# sensor_eeprom_v3_0.net
KiCad netlist of a schematic drawn in EAGLE
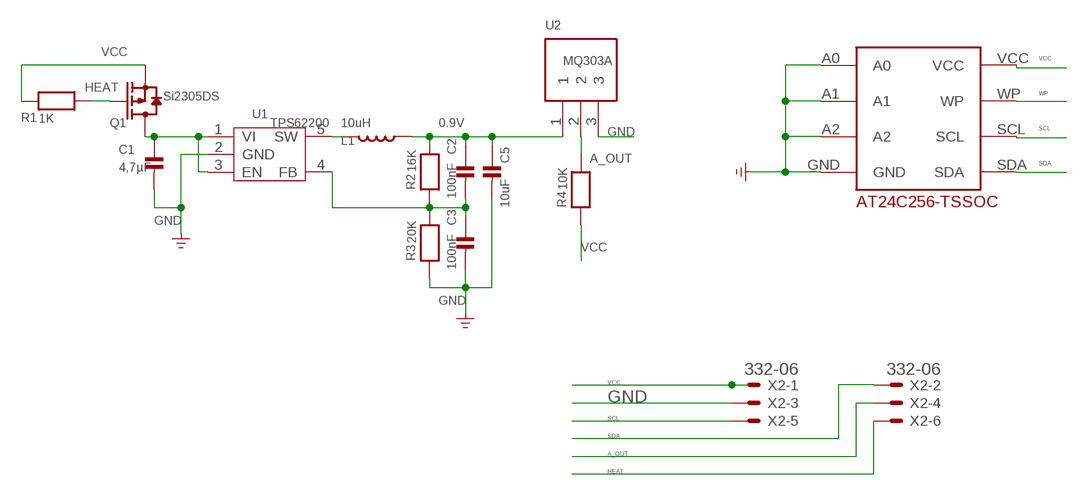
[diagram p0: schematic, sheet 1]

(export (version "E")
  (design (tool "Eeschema 10.0.6"))
  (components
    (comp (ref "C1")
      (value "4,7µF")
      (footprint "eagle-import:0805")
      (libsource (lib "eagle-import") (part "CAP_CERAMIC0805"))
    )
    (comp (ref "C2")
      (value "100nF")
      (footprint "eagle-import:0805")
      (libsource (lib "eagle-import") (part "CAP_CERAMIC0805"))
    )
    (comp (ref "C3")
      (value "100nF")
      (footprint "eagle-import:0805")
      (libsource (lib "eagle-import") (part "CAP_CERAMIC0805"))
    )
    (comp (ref "C5")
      (value "10uF")
      (footprint "eagle-import:0805")
      (libsource (lib "eagle-import") (part "CAP_CERAMIC0805"))
    )
    (comp (ref "L1")
      (value "10uH")
      (footprint "eagle-import:PIO73")
      (libsource (lib "eagle-import") (part "L'PIO73'"))
    )
    (comp (ref "Q1")
      (value "Si2305DS")
      (footprint "eagle-import:SOT23")
      (libsource (lib "eagle-import") (part "MOSFET-P'SI2323CDS/SI2305DS{lt}BR{gt}'"))
    )
    (comp (ref "R1")
      (value "1K")
      (footprint "eagle-import:0805")
      (libsource (lib "eagle-import") (part "RESISTOR0805"))
    )
    (comp (ref "R2")
      (value "16K")
      (footprint "eagle-import:0805")
      (libsource (lib "eagle-import") (part "RESISTOR0805"))
    )
    (comp (ref "R3")
      (value "20K")
      (footprint "eagle-import:0805")
      (libsource (lib "eagle-import") (part "RESISTOR0805"))
    )
    (comp (ref "R4")
      (value "10K")
      (footprint "eagle-import:0805")
      (libsource (lib "eagle-import") (part "RESISTOR0805"))
    )
    (comp (ref "U$1")
      (value "DECADE-AT24C256-10TI-2.7")
      (footprint "eagle-import:DECADE-AT24CXX")
      (libsource (lib "eagle-import") (part "DECADE-AT24C256-10TI-2.7"))
    )
    (comp (ref "U1")
      (value "TPS62200")
      (footprint "eagle-import:SOT23-5")
      (libsource (lib "eagle-import") (part "TPS62200DBV"))
    )
    (comp (ref "U2")
      (value "MQ303A")
      (footprint "eagle-import:MQ303A")
      (libsource (lib "eagle-import") (part "MQ303A"))
    )
    (comp (ref "X2")
      (value "332-06")
      (footprint "eagle-import:332-06")
      (libsource (lib "eagle-import") (part "332-06"))
    )
  )
  (nets
    (net (code "1") (name "/0.9V") (class "Default")
      (node (ref "C2") (pin "1") (pinfunction "P$1_1") (pintype "passive"))
      (node (ref "C5") (pin "1") (pinfunction "P$1_1") (pintype "passive"))
      (node (ref "L1") (pin "2") (pinfunction "2_2") (pintype "passive"))
      (node (ref "R2") (pin "2") (pinfunction "2_2") (pintype "passive"))
      (node (ref "U2") (pin "1") (pinfunction "1_1") (pintype "bidirectional"))
    )
    (net (code "2") (name "/A_OUT") (class "Default")
      (node (ref "R4") (pin "2") (pinfunction "2_2") (pintype "passive"))
      (node (ref "U2") (pin "2") (pinfunction "2_2") (pintype "bidirectional"))
      (node (ref "X2") (pin "4") (pinfunction "S_4") (pintype "passive"))
    )
    (net (code "3") (name "/HEAT") (class "Default")
      (node (ref "Q1") (pin "1") (pinfunction "G_1") (pintype "passive"))
      (node (ref "R1") (pin "2") (pinfunction "2_2") (pintype "passive"))
      (node (ref "X2") (pin "6") (pinfunction "S_6") (pintype "passive"))
    )
    (net (code "4") (name "/SCL") (class "Default")
      (node (ref "U$1") (pin "SCL") (pinfunction "SCL_SCL") (pintype "bidirectional"))
      (node (ref "X2") (pin "5") (pinfunction "S_5") (pintype "passive"))
    )
    (net (code "5") (name "/SDA") (class "Default")
      (node (ref "U$1") (pin "SDA") (pinfunction "SDA_SDA") (pintype "bidirectional"))
      (node (ref "X2") (pin "2") (pinfunction "S_2") (pintype "passive"))
    )
    (net (code "6") (name "/VCC") (class "Default")
      (node (ref "Q1") (pin "2") (pinfunction "S_2") (pintype "passive"))
      (node (ref "R1") (pin "1") (pinfunction "1_1") (pintype "passive"))
      (node (ref "R4") (pin "1") (pinfunction "1_1") (pintype "passive"))
      (node (ref "U$1") (pin "VCC") (pinfunction "VCC_VCC") (pintype "bidirectional"))
      (node (ref "X2") (pin "1") (pinfunction "S_1") (pintype "passive"))
    )
    (net (code "7") (name "/WP") (class "Default")
      (node (ref "U$1") (pin "WP") (pinfunction "WP_WP") (pintype "bidirectional"))
    )
    (net (code "8") (name "GND_POWER") (class "Default")
      (node (ref "C1") (pin "2") (pinfunction "P$2_2") (pintype "passive"))
      (node (ref "C3") (pin "2") (pinfunction "P$2_2") (pintype "passive"))
      (node (ref "C5") (pin "2") (pinfunction "P$2_2") (pintype "passive"))
      (node (ref "R3") (pin "1") (pinfunction "1_1") (pintype "passive"))
      (node (ref "U$1") (pin "A0") (pinfunction "A0_A0") (pintype "bidirectional"))
      (node (ref "U$1") (pin "A1") (pinfunction "A1_A1") (pintype "bidirectional"))
      (node (ref "U$1") (pin "A2") (pinfunction "A2_A2") (pintype "bidirectional"))
      (node (ref "U$1") (pin "GND") (pinfunction "GND_GND") (pintype "bidirectional"))
      (node (ref "U1") (pin "2") (pinfunction "GND_2") (pintype "power_in"))
      (node (ref "U2") (pin "3") (pinfunction "3_3") (pintype "bidirectional"))
      (node (ref "X2") (pin "3") (pinfunction "S_3") (pintype "passive"))
    )
    (net (code "9") (name "Net-(C1-P$1)") (class "Default")
      (node (ref "C1") (pin "1") (pinfunction "P$1_1") (pintype "passive"))
      (node (ref "Q1") (pin "3") (pinfunction "D_3") (pintype "passive"))
      (node (ref "U1") (pin "1") (pinfunction "VI_1") (pintype "input"))
      (node (ref "U1") (pin "3") (pinfunction "EN_3") (pintype "input"))
    )
    (net (code "10") (name "Net-(C2-P$2)") (class "Default")
      (node (ref "C2") (pin "2") (pinfunction "P$2_2") (pintype "passive"))
      (node (ref "C3") (pin "1") (pinfunction "P$1_1") (pintype "passive"))
      (node (ref "R2") (pin "1") (pinfunction "1_1") (pintype "passive"))
      (node (ref "R3") (pin "2") (pinfunction "2_2") (pintype "passive"))
      (node (ref "U1") (pin "4") (pinfunction "FB_4") (pintype "input"))
    )
    (net (code "11") (name "Net-(U1-SW)") (class "Default")
      (node (ref "L1") (pin "1") (pinfunction "1_1") (pintype "passive"))
      (node (ref "U1") (pin "5") (pinfunction "SW_5") (pintype "bidirectional"))
    )
  )
)
